# 32U4_Breakout-v11.net
KiCad netlist of a schematic drawn in EAGLE
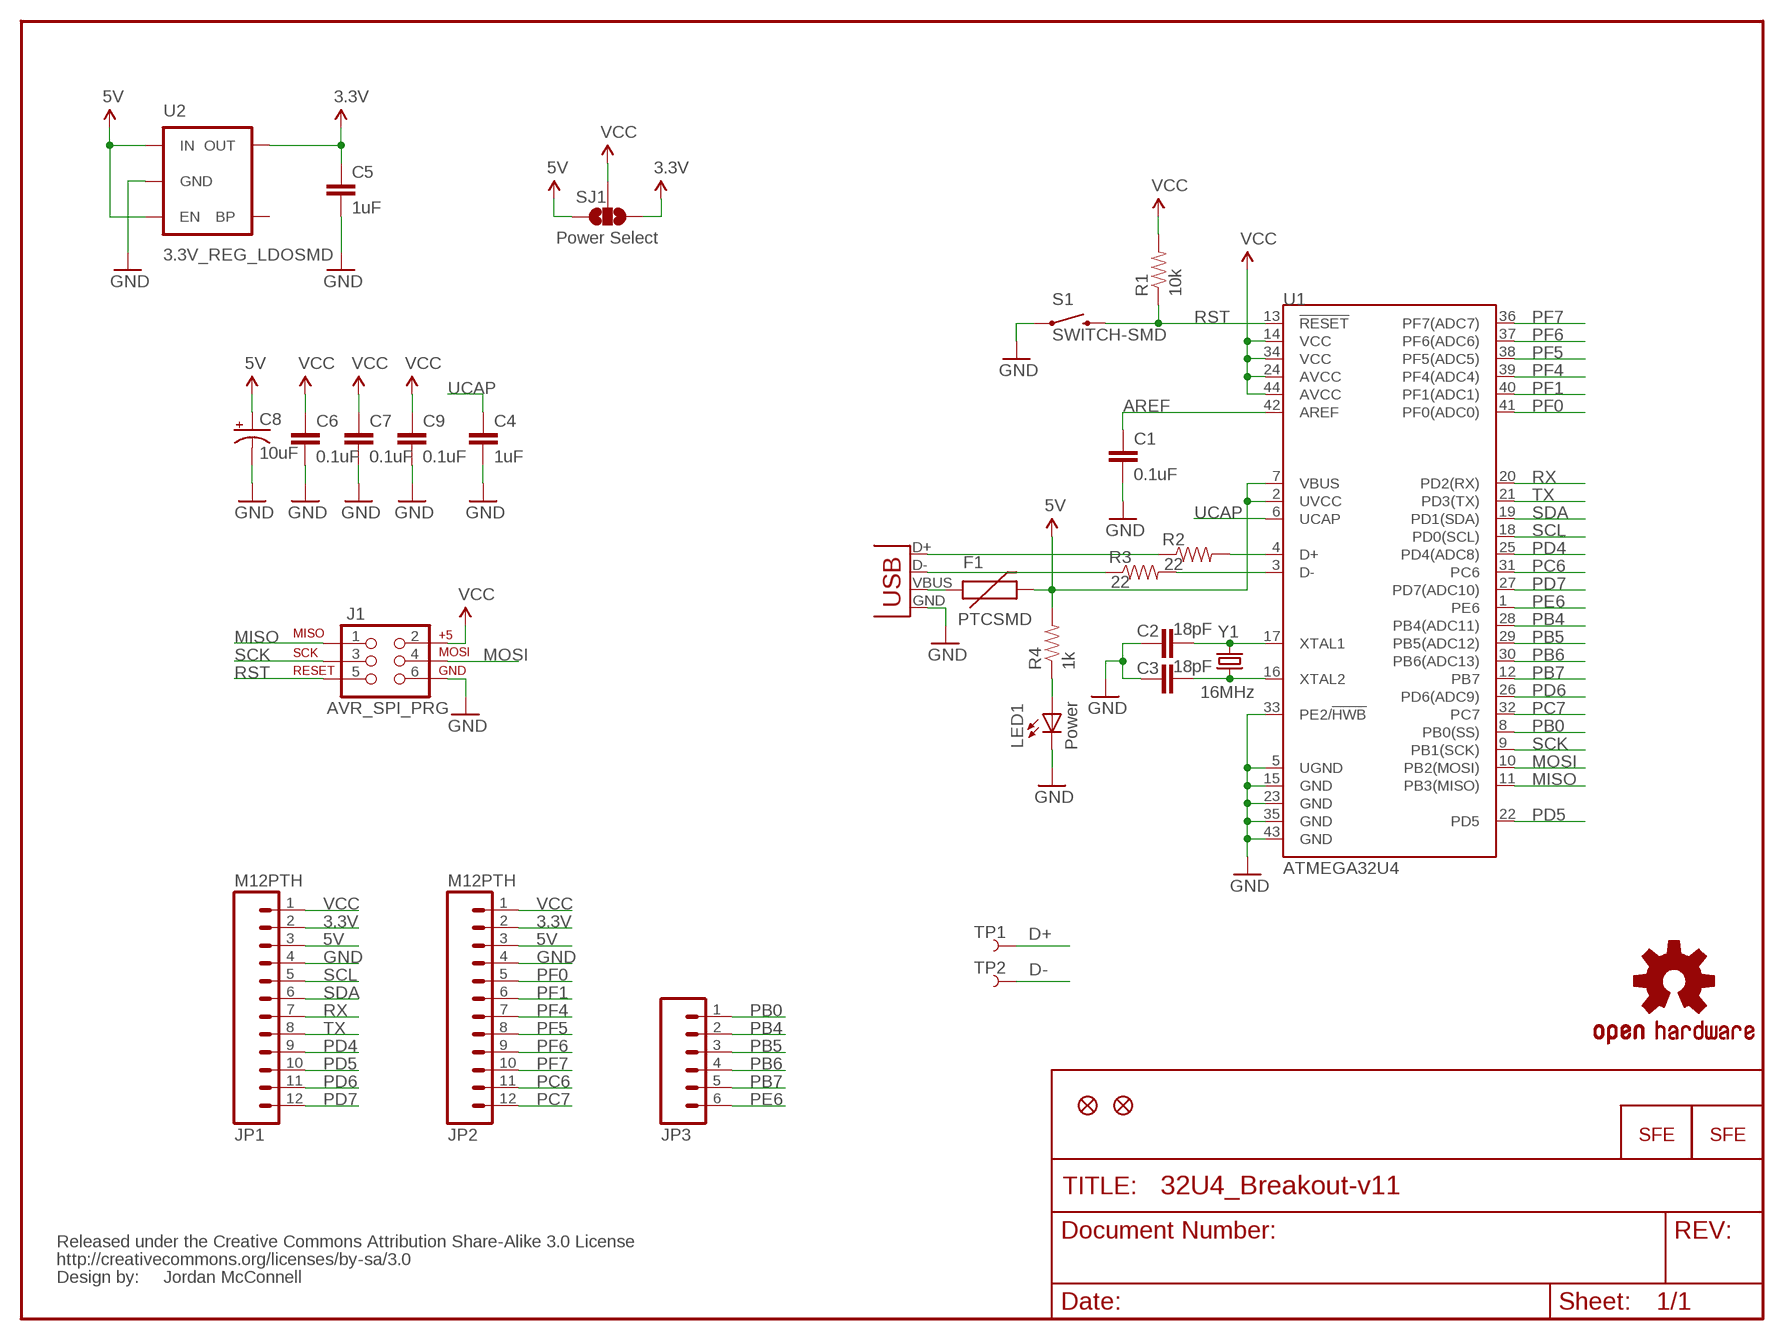
[diagram p0: schematic, sheet 1]

(export (version "E")
  (design (tool "Eeschema 10.0.6"))
  (components
    (comp (ref "C1")
      (value "0.1uF")
      (footprint "eagle-import:0402-CAP")
      (libsource (lib "eagle-import") (part "CAP0402-CAP"))
    )
    (comp (ref "C2")
      (value "18pF")
      (footprint "eagle-import:0402-CAP")
      (libsource (lib "eagle-import") (part "CAP0402-CAP"))
    )
    (comp (ref "C3")
      (value "18pF")
      (footprint "eagle-import:0402-CAP")
      (libsource (lib "eagle-import") (part "CAP0402-CAP"))
    )
    (comp (ref "C4")
      (value "1uF")
      (footprint "eagle-import:0402-CAP")
      (libsource (lib "eagle-import") (part "CAP0402-CAP"))
    )
    (comp (ref "C5")
      (value "1uF")
      (footprint "eagle-import:0402-CAP")
      (libsource (lib "eagle-import") (part "CAP0402-CAP"))
    )
    (comp (ref "C6")
      (value "0.1uF")
      (footprint "eagle-import:0402-CAP")
      (libsource (lib "eagle-import") (part "CAP0402-CAP"))
    )
    (comp (ref "C7")
      (value "0.1uF")
      (footprint "eagle-import:0402-CAP")
      (libsource (lib "eagle-import") (part "CAP0402-CAP"))
    )
    (comp (ref "C8")
      (value "10uF")
      (footprint "eagle-import:EIA3216")
      (libsource (lib "eagle-import") (part "CAP_POL1206"))
    )
    (comp (ref "C9")
      (value "0.1uF")
      (footprint "eagle-import:0402-CAP")
      (libsource (lib "eagle-import") (part "CAP0402-CAP"))
    )
    (comp (ref "F1")
      (value "PTCSMD")
      (footprint "eagle-import:PTC-1206")
      (libsource (lib "eagle-import") (part "PTCSMD"))
    )
    (comp (ref "J1")
      (value "AVR_SPI_PRG")
      (footprint "eagle-import:2X3")
      (libsource (lib "eagle-import") (part "AVR_SPI_PRG_6PTH"))
    )
    (comp (ref "JP1")
      (value "M12PTH")
      (footprint "eagle-import:1X12")
      (libsource (lib "eagle-import") (part "M12PTH"))
    )
    (comp (ref "JP2")
      (value "M12PTH")
      (footprint "eagle-import:1X12")
      (libsource (lib "eagle-import") (part "M12PTH"))
    )
    (comp (ref "JP3")
      (value "M06SIP")
      (footprint "eagle-import:1X06")
      (libsource (lib "eagle-import") (part "M06SIP"))
    )
    (comp (ref "JP4")
      (value "LOGO-SFENEW")
      (footprint "eagle-import:SFE-NEW-WEBLOGO")
      (libsource (lib "eagle-import") (part "LOGO-SFENEW"))
    )
    (comp (ref "JP5")
      (value "LOGO-SFESK")
      (footprint "eagle-import:SFE-LOGO-FLAME")
      (libsource (lib "eagle-import") (part "LOGO-SFESK"))
    )
    (comp (ref "JP6")
      (value "FIDUCIALUFIDUCIAL")
      (footprint "eagle-import:MICRO-FIDUCIAL")
      (libsource (lib "eagle-import") (part "FIDUCIALUFIDUCIAL"))
    )
    (comp (ref "JP7")
      (value "FIDUCIALUFIDUCIAL")
      (footprint "eagle-import:MICRO-FIDUCIAL")
      (libsource (lib "eagle-import") (part "FIDUCIALUFIDUCIAL"))
    )
    (comp (ref "LED1")
      (value "Power")
      (footprint "eagle-import:LED-0603")
      (libsource (lib "eagle-import") (part "LED0603"))
    )
    (comp (ref "R1")
      (value "10k")
      (footprint "eagle-import:0402-RES")
      (libsource (lib "eagle-import") (part "RESISTOR0402-RES"))
    )
    (comp (ref "R2")
      (value "22")
      (footprint "eagle-import:0402-RES")
      (libsource (lib "eagle-import") (part "RESISTOR0402-RES"))
    )
    (comp (ref "R3")
      (value "22")
      (footprint "eagle-import:0402-RES")
      (libsource (lib "eagle-import") (part "RESISTOR0402-RES"))
    )
    (comp (ref "R4")
      (value "1k")
      (footprint "eagle-import:0402-RES")
      (libsource (lib "eagle-import") (part "RESISTOR0402-RES"))
    )
    (comp (ref "S1")
      (value "SWITCH-SMD")
      (footprint "eagle-import:TACTILE_SWITCH_SMD")
      (libsource (lib "eagle-import") (part "SWITCH-MOMENTARY-2SMD"))
    )
    (comp (ref "SJ1")
      (value "Power Select")
      (footprint "eagle-import:SJ_3_PASTE2&3")
      (libsource (lib "eagle-import") (part "SOLDERJUMPER_2WAYPASTE2&3"))
    )
    (comp (ref "TP1")
      (value "TEST-POINT3")
      (footprint "eagle-import:PAD.03X.03")
      (libsource (lib "eagle-import") (part "TEST-POINT3"))
    )
    (comp (ref "TP2")
      (value "TEST-POINT3")
      (footprint "eagle-import:PAD.03X.03")
      (libsource (lib "eagle-import") (part "TEST-POINT3"))
    )
    (comp (ref "U$6")
      (value "OSHW-LOGOM")
      (footprint "eagle-import:OSHW-LOGO-M")
      (libsource (lib "eagle-import") (part "OSHW-LOGOM"))
    )
    (comp (ref "U$7")
      (value "CREATIVE_COMMONS")
      (footprint "eagle-import:CREATIVE_COMMONS")
      (libsource (lib "eagle-import") (part "CREATIVE_COMMONS"))
    )
    (comp (ref "U1")
      (value "ATMEGA32U4")
      (footprint "eagle-import:QFN-44-NOPAD")
      (libsource (lib "eagle-import") (part "ATMEGA32U4QFN2"))
    )
    (comp (ref "U2")
      (value "3.3V_REG_LDOSMD")
      (footprint "eagle-import:SOT23-5")
      (libsource (lib "eagle-import") (part "V_REG_LDOSMD"))
    )
    (comp (ref "X1")
      (value "USBSMD")
      (footprint "eagle-import:USB-MINIB")
      (libsource (lib "eagle-import") (part "USBSMD"))
    )
    (comp (ref "Y1")
      (value "16MHz")
      (footprint "eagle-import:CRYSTAL-SMD-5X3")
      (libsource (lib "eagle-import") (part "CRYSTAL5X3"))
    )
  )
  (nets
    (net (code "1") (name "/AREF") (class "Default")
      (node (ref "C1") (pin "1") (pinfunction "1_1") (pintype "passive"))
      (node (ref "U1") (pin "42") (pinfunction "AREF_42") (pintype "bidirectional"))
    )
    (net (code "2") (name "/D+") (class "Default")
      (node (ref "R2") (pin "1") (pinfunction "1_1") (pintype "passive"))
      (node (ref "TP1") (pin "P$1") (pinfunction "1_P$1") (pintype "bidirectional"))
      (node (ref "X1") (pin "D+") (pinfunction "D+_D+") (pintype "bidirectional"))
    )
    (net (code "3") (name "/D-") (class "Default")
      (node (ref "R3") (pin "1") (pinfunction "1_1") (pintype "passive"))
      (node (ref "TP2") (pin "P$1") (pinfunction "1_P$1") (pintype "bidirectional"))
      (node (ref "X1") (pin "D-") (pinfunction "D-_D-") (pintype "bidirectional"))
    )
    (net (code "4") (name "/MISO") (class "Default")
      (node (ref "J1") (pin "1") (pinfunction "1_1") (pintype "passive"))
      (node (ref "U1") (pin "11") (pinfunction "PB3(MISO)_11") (pintype "bidirectional"))
    )
    (net (code "5") (name "/MOSI") (class "Default")
      (node (ref "J1") (pin "4") (pinfunction "4_4") (pintype "passive"))
      (node (ref "U1") (pin "10") (pinfunction "PB2(MOSI)_10") (pintype "bidirectional"))
    )
    (net (code "6") (name "/PB0") (class "Default")
      (node (ref "JP3") (pin "1") (pinfunction "1_1") (pintype "passive"))
      (node (ref "U1") (pin "8") (pinfunction "PB0(SS)_8") (pintype "bidirectional"))
    )
    (net (code "7") (name "/PB4") (class "Default")
      (node (ref "JP3") (pin "2") (pinfunction "2_2") (pintype "passive"))
      (node (ref "U1") (pin "28") (pinfunction "PB4(ADC11)_28") (pintype "bidirectional"))
    )
    (net (code "8") (name "/PB5") (class "Default")
      (node (ref "JP3") (pin "3") (pinfunction "3_3") (pintype "passive"))
      (node (ref "U1") (pin "29") (pinfunction "PB5(ADC12)_29") (pintype "bidirectional"))
    )
    (net (code "9") (name "/PB6") (class "Default")
      (node (ref "JP3") (pin "4") (pinfunction "4_4") (pintype "passive"))
      (node (ref "U1") (pin "30") (pinfunction "PB6(ADC13)_30") (pintype "bidirectional"))
    )
    (net (code "10") (name "/PB7") (class "Default")
      (node (ref "JP3") (pin "5") (pinfunction "5_5") (pintype "passive"))
      (node (ref "U1") (pin "12") (pinfunction "PB7_12") (pintype "bidirectional"))
    )
    (net (code "11") (name "/PC6") (class "Default")
      (node (ref "JP2") (pin "11") (pinfunction "11_11") (pintype "passive"))
      (node (ref "U1") (pin "31") (pinfunction "PC6_31") (pintype "bidirectional"))
    )
    (net (code "12") (name "/PC7") (class "Default")
      (node (ref "JP2") (pin "12") (pinfunction "12_12") (pintype "passive"))
      (node (ref "U1") (pin "32") (pinfunction "PC7_32") (pintype "bidirectional"))
    )
    (net (code "13") (name "/PD4") (class "Default")
      (node (ref "JP1") (pin "9") (pinfunction "9_9") (pintype "passive"))
      (node (ref "U1") (pin "25") (pinfunction "PD4(ADC8)_25") (pintype "bidirectional"))
    )
    (net (code "14") (name "/PD5") (class "Default")
      (node (ref "JP1") (pin "10") (pinfunction "10_10") (pintype "passive"))
      (node (ref "U1") (pin "22") (pinfunction "PD5_22") (pintype "bidirectional"))
    )
    (net (code "15") (name "/PD6") (class "Default")
      (node (ref "JP1") (pin "11") (pinfunction "11_11") (pintype "passive"))
      (node (ref "U1") (pin "26") (pinfunction "PD6(ADC9)_26") (pintype "bidirectional"))
    )
    (net (code "16") (name "/PD7") (class "Default")
      (node (ref "JP1") (pin "12") (pinfunction "12_12") (pintype "passive"))
      (node (ref "U1") (pin "27") (pinfunction "PD7(ADC10)_27") (pintype "bidirectional"))
    )
    (net (code "17") (name "/PE6") (class "Default")
      (node (ref "JP3") (pin "6") (pinfunction "6_6") (pintype "passive"))
      (node (ref "U1") (pin "1") (pinfunction "PE6_1") (pintype "bidirectional"))
    )
    (net (code "18") (name "/PF0") (class "Default")
      (node (ref "JP2") (pin "5") (pinfunction "5_5") (pintype "passive"))
      (node (ref "U1") (pin "41") (pinfunction "PF0(ADC0)_41") (pintype "bidirectional"))
    )
    (net (code "19") (name "/PF1") (class "Default")
      (node (ref "JP2") (pin "6") (pinfunction "6_6") (pintype "passive"))
      (node (ref "U1") (pin "40") (pinfunction "PF1(ADC1)_40") (pintype "bidirectional"))
    )
    (net (code "20") (name "/PF4") (class "Default")
      (node (ref "JP2") (pin "7") (pinfunction "7_7") (pintype "passive"))
      (node (ref "U1") (pin "39") (pinfunction "PF4(ADC4)_39") (pintype "bidirectional"))
    )
    (net (code "21") (name "/PF5") (class "Default")
      (node (ref "JP2") (pin "8") (pinfunction "8_8") (pintype "passive"))
      (node (ref "U1") (pin "38") (pinfunction "PF5(ADC5)_38") (pintype "bidirectional"))
    )
    (net (code "22") (name "/PF6") (class "Default")
      (node (ref "JP2") (pin "9") (pinfunction "9_9") (pintype "passive"))
      (node (ref "U1") (pin "37") (pinfunction "PF6(ADC6)_37") (pintype "bidirectional"))
    )
    (net (code "23") (name "/PF7") (class "Default")
      (node (ref "JP2") (pin "10") (pinfunction "10_10") (pintype "passive"))
      (node (ref "U1") (pin "36") (pinfunction "PF7(ADC7)_36") (pintype "bidirectional"))
    )
    (net (code "24") (name "/RST") (class "Default")
      (node (ref "J1") (pin "5") (pinfunction "5_5") (pintype "passive"))
      (node (ref "R1") (pin "1") (pinfunction "1_1") (pintype "passive"))
      (node (ref "S1") (pin "3") (pinfunction "2_3") (pintype "passive"))
      (node (ref "U1") (pin "13") (pinfunction "~{RESET}_13") (pintype "bidirectional"))
    )
    (net (code "25") (name "/RX") (class "Default")
      (node (ref "JP1") (pin "7") (pinfunction "7_7") (pintype "passive"))
      (node (ref "U1") (pin "20") (pinfunction "PD2(RX)_20") (pintype "bidirectional"))
    )
    (net (code "26") (name "/SCK") (class "Default")
      (node (ref "J1") (pin "3") (pinfunction "3_3") (pintype "passive"))
      (node (ref "U1") (pin "9") (pinfunction "PB1(SCK)_9") (pintype "bidirectional"))
    )
    (net (code "27") (name "/SCL") (class "Default")
      (node (ref "JP1") (pin "5") (pinfunction "5_5") (pintype "passive"))
      (node (ref "U1") (pin "18") (pinfunction "PD0(SCL)_18") (pintype "bidirectional"))
    )
    (net (code "28") (name "/SDA") (class "Default")
      (node (ref "JP1") (pin "6") (pinfunction "6_6") (pintype "passive"))
      (node (ref "U1") (pin "19") (pinfunction "PD1(SDA)_19") (pintype "bidirectional"))
    )
    (net (code "29") (name "/TX") (class "Default")
      (node (ref "JP1") (pin "8") (pinfunction "8_8") (pintype "passive"))
      (node (ref "U1") (pin "21") (pinfunction "PD3(TX)_21") (pintype "bidirectional"))
    )
    (net (code "30") (name "/UCAP") (class "Default")
      (node (ref "C4") (pin "1") (pinfunction "1_1") (pintype "passive"))
      (node (ref "U1") (pin "6") (pinfunction "UCAP_6") (pintype "bidirectional"))
    )
    (net (code "31") (name "3.3V") (class "Default")
      (node (ref "C5") (pin "1") (pinfunction "1_1") (pintype "passive"))
      (node (ref "JP1") (pin "2") (pinfunction "2_2") (pintype "passive"))
      (node (ref "JP2") (pin "2") (pinfunction "2_2") (pintype "passive"))
      (node (ref "SJ1") (pin "1") (pinfunction "1_1") (pintype "passive"))
      (node (ref "U2") (pin "5") (pinfunction "OUT_5") (pintype "passive"))
    )
    (net (code "32") (name "5V") (class "Default")
      (node (ref "C8") (pin "A") (pinfunction "+_A") (pintype "passive"))
      (node (ref "F1") (pin "2") (pinfunction "2_2") (pintype "bidirectional"))
      (node (ref "JP1") (pin "3") (pinfunction "3_3") (pintype "passive"))
      (node (ref "JP2") (pin "3") (pinfunction "3_3") (pintype "passive"))
      (node (ref "R4") (pin "2") (pinfunction "2_2") (pintype "passive"))
      (node (ref "SJ1") (pin "3") (pinfunction "3_3") (pintype "passive"))
      (node (ref "U1") (pin "2") (pinfunction "UVCC_2") (pintype "bidirectional"))
      (node (ref "U1") (pin "7") (pinfunction "VBUS_7") (pintype "bidirectional"))
      (node (ref "U2") (pin "1") (pinfunction "IN_1") (pintype "input"))
      (node (ref "U2") (pin "3") (pinfunction "EN_3") (pintype "input"))
    )
    (net (code "33") (name "GND") (class "Default")
      (node (ref "C1") (pin "2") (pinfunction "2_2") (pintype "passive"))
      (node (ref "C2") (pin "1") (pinfunction "1_1") (pintype "passive"))
      (node (ref "C3") (pin "1") (pinfunction "1_1") (pintype "passive"))
      (node (ref "C4") (pin "2") (pinfunction "2_2") (pintype "passive"))
      (node (ref "C5") (pin "2") (pinfunction "2_2") (pintype "passive"))
      (node (ref "C6") (pin "2") (pinfunction "2_2") (pintype "passive"))
      (node (ref "C7") (pin "2") (pinfunction "2_2") (pintype "passive"))
      (node (ref "C8") (pin "C") (pinfunction "-_C") (pintype "passive"))
      (node (ref "C9") (pin "2") (pinfunction "2_2") (pintype "passive"))
      (node (ref "J1") (pin "6") (pinfunction "6_6") (pintype "passive"))
      (node (ref "JP1") (pin "4") (pinfunction "4_4") (pintype "passive"))
      (node (ref "JP2") (pin "4") (pinfunction "4_4") (pintype "passive"))
      (node (ref "LED1") (pin "C") (pinfunction "C_C") (pintype "passive"))
      (node (ref "S1") (pin "1") (pinfunction "1_1") (pintype "passive"))
      (node (ref "U1") (pin "15") (pinfunction "GND_15") (pintype "bidirectional"))
      (node (ref "U1") (pin "23") (pinfunction "GND_23") (pintype "bidirectional"))
      (node (ref "U1") (pin "33") (pinfunction "PE2/~{HWB}_33") (pintype "bidirectional"))
      (node (ref "U1") (pin "35") (pinfunction "GND_35") (pintype "bidirectional"))
      (node (ref "U1") (pin "43") (pinfunction "GND_43") (pintype "bidirectional"))
      (node (ref "U1") (pin "5") (pinfunction "UGND_5") (pintype "bidirectional"))
      (node (ref "U2") (pin "2") (pinfunction "GND_2") (pintype "input"))
      (node (ref "X1") (pin "GND") (pinfunction "GND_GND") (pintype "bidirectional"))
    )
    (net (code "34") (name "Net-(F1-Pad1)") (class "Default")
      (node (ref "F1") (pin "1") (pinfunction "1_1") (pintype "bidirectional"))
      (node (ref "X1") (pin "VBUS") (pinfunction "VBUS_VBUS") (pintype "bidirectional"))
    )
    (net (code "35") (name "Net-(LED1-PadA)") (class "Default")
      (node (ref "LED1") (pin "A") (pinfunction "A_A") (pintype "passive"))
      (node (ref "R4") (pin "1") (pinfunction "1_1") (pintype "passive"))
    )
    (net (code "36") (name "Net-(U1-D+)") (class "Default")
      (node (ref "R2") (pin "2") (pinfunction "2_2") (pintype "passive"))
      (node (ref "U1") (pin "4") (pinfunction "D+_4") (pintype "bidirectional"))
    )
    (net (code "37") (name "Net-(U1-D-)") (class "Default")
      (node (ref "R3") (pin "2") (pinfunction "2_2") (pintype "passive"))
      (node (ref "U1") (pin "3") (pinfunction "D-_3") (pintype "bidirectional"))
    )
    (net (code "38") (name "Net-(U1-XTAL1)") (class "Default")
      (node (ref "C2") (pin "2") (pinfunction "2_2") (pintype "passive"))
      (node (ref "U1") (pin "17") (pinfunction "XTAL1_17") (pintype "bidirectional"))
      (node (ref "Y1") (pin "3") (pinfunction "2_3") (pintype "passive"))
    )
    (net (code "39") (name "Net-(U1-XTAL2)") (class "Default")
      (node (ref "C3") (pin "2") (pinfunction "2_2") (pintype "passive"))
      (node (ref "U1") (pin "16") (pinfunction "XTAL2_16") (pintype "bidirectional"))
      (node (ref "Y1") (pin "1") (pinfunction "1_1") (pintype "passive"))
    )
    (net (code "40") (name "VCC") (class "Default")
      (node (ref "C6") (pin "1") (pinfunction "1_1") (pintype "passive"))
      (node (ref "C7") (pin "1") (pinfunction "1_1") (pintype "passive"))
      (node (ref "C9") (pin "1") (pinfunction "1_1") (pintype "passive"))
      (node (ref "J1") (pin "2") (pinfunction "2_2") (pintype "passive"))
      (node (ref "JP1") (pin "1") (pinfunction "1_1") (pintype "passive"))
      (node (ref "JP2") (pin "1") (pinfunction "1_1") (pintype "passive"))
      (node (ref "R1") (pin "2") (pinfunction "2_2") (pintype "passive"))
      (node (ref "SJ1") (pin "2") (pinfunction "2_2") (pintype "passive"))
      (node (ref "U1") (pin "14") (pinfunction "VCC_14") (pintype "bidirectional"))
      (node (ref "U1") (pin "24") (pinfunction "AVCC_24") (pintype "bidirectional"))
      (node (ref "U1") (pin "34") (pinfunction "VCC_34") (pintype "bidirectional"))
      (node (ref "U1") (pin "44") (pinfunction "AVCC_44") (pintype "bidirectional"))
    )
    (net (code "41") (name "unconnected-(U2-BP-Pad4)") (class "Default")
      (node (ref "U2") (pin "4") (pinfunction "BP_4") (pintype "input"))
    )
  )
)
